# mfrhp.net
KiCad netlist of a schematic drawn in EAGLE
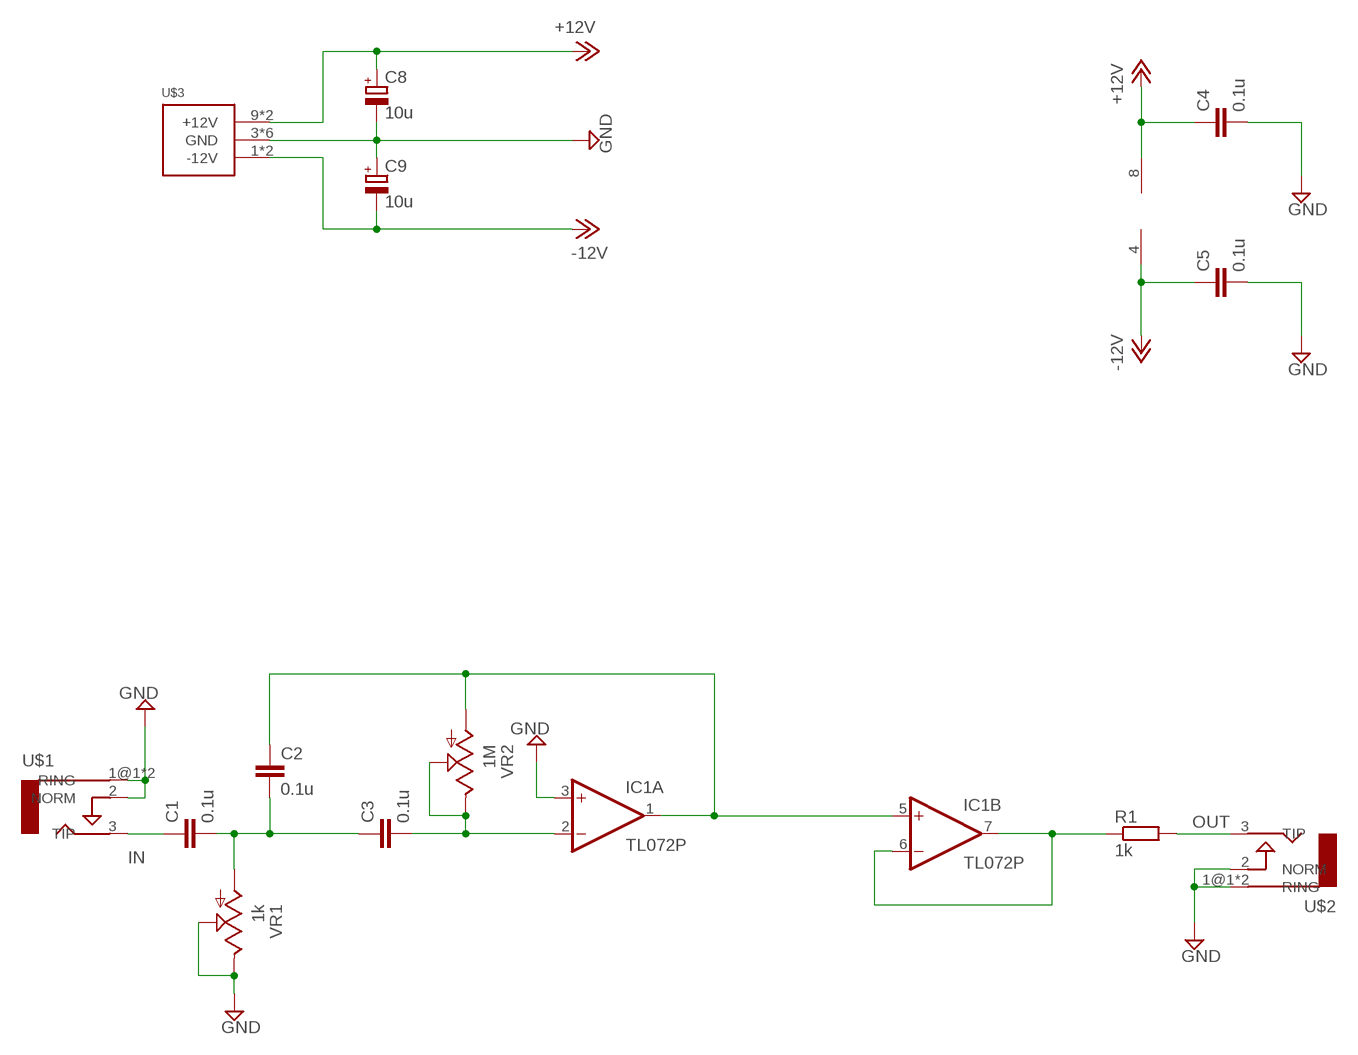
[diagram p0: schematic, sheet 1]

(export (version "E")
  (design (tool "Eeschema 10.0.6"))
  (components
    (comp (ref "C1")
      (value "0.1u")
      (footprint "eagle-import:C050-025X075")
      (libsource (lib "eagle-import") (part "C-EU050-025X075"))
    )
    (comp (ref "C2")
      (value "0.1u")
      (footprint "eagle-import:C050-025X075")
      (libsource (lib "eagle-import") (part "C-EU050-025X075"))
    )
    (comp (ref "C3")
      (value "0.1u")
      (footprint "eagle-import:C050-025X075")
      (libsource (lib "eagle-import") (part "C-EU050-025X075"))
    )
    (comp (ref "C4")
      (value "0.1u")
      (footprint "eagle-import:C025-025X050")
      (libsource (lib "eagle-import") (part "C-EU025-025X050"))
    )
    (comp (ref "C5")
      (value "0.1u")
      (footprint "eagle-import:C025-025X050")
      (libsource (lib "eagle-import") (part "C-EU025-025X050"))
    )
    (comp (ref "C8")
      (value "10u")
      (footprint "eagle-import:E2,5-5")
      (libsource (lib "eagle-import") (part "CPOL-EUE2.5-5"))
    )
    (comp (ref "C9")
      (value "10u")
      (footprint "eagle-import:E2,5-5")
      (libsource (lib "eagle-import") (part "CPOL-EUE2.5-5"))
    )
    (comp (ref "IC1")
      (value "TL072P")
      (footprint "eagle-import:DIL08")
      (libsource (lib "eagle-import") (part "TL072P"))
    )
    (comp (ref "R1")
      (value "1k")
      (footprint "eagle-import:0207_2V")
      (libsource (lib "eagle-import") (part "R-EU_0207/2V"))
    )
    (comp (ref "U$1")
      (value "AUDIO-JACKERTHENVAR")
      (footprint "eagle-import:ERTHENVAR-JACK")
      (libsource (lib "eagle-import") (part "AUDIO-JACKERTHENVAR"))
    )
    (comp (ref "U$2")
      (value "AUDIO-JACKERTHENVAR")
      (footprint "eagle-import:ERTHENVAR-JACK")
      (libsource (lib "eagle-import") (part "AUDIO-JACKERTHENVAR"))
    )
    (comp (ref "U$3")
      (value "POWER_SIMPLE10")
      (footprint "eagle-import:POWER_10")
      (libsource (lib "eagle-import") (part "POWER_SIMPLE10"))
    )
    (comp (ref "VR1")
      (value "1k")
      (footprint "eagle-import:9MM_SNAP-IN_POT")
      (libsource (lib "eagle-import") (part "9MM_SNAP-IN_POT_"))
    )
    (comp (ref "VR2")
      (value "1M")
      (footprint "eagle-import:9MM_SNAP-IN_POT")
      (libsource (lib "eagle-import") (part "9MM_SNAP-IN_POT_"))
    )
  )
  (nets
    (net (code "1") (name "+12V") (class "Default")
      (node (ref "C4") (pin "1") (pinfunction "1_1") (pintype "passive"))
      (node (ref "C8") (pin "+") (pinfunction "+_+") (pintype "passive"))
      (node (ref "IC1") (pin "8") (pinfunction "V+_8") (pintype "power_in"))
      (node (ref "U$3") (pin "10") (pinfunction "+12V_10") (pintype "bidirectional"))
      (node (ref "U$3") (pin "9") (pinfunction "+12V_9") (pintype "bidirectional"))
    )
    (net (code "2") (name "-12V") (class "Default")
      (node (ref "C5") (pin "1") (pinfunction "1_1") (pintype "passive"))
      (node (ref "C9") (pin "-") (pinfunction "-_-") (pintype "passive"))
      (node (ref "IC1") (pin "4") (pinfunction "V-_4") (pintype "power_in"))
      (node (ref "U$3") (pin "1") (pinfunction "-12V_1") (pintype "bidirectional"))
      (node (ref "U$3") (pin "2") (pinfunction "-12V_2") (pintype "bidirectional"))
    )
    (net (code "3") (name "/IN") (class "Default")
      (node (ref "C1") (pin "1") (pinfunction "1_1") (pintype "passive"))
      (node (ref "U$1") (pin "3") (pinfunction "TIP_3") (pintype "bidirectional"))
    )
    (net (code "4") (name "/OUT") (class "Default")
      (node (ref "R1") (pin "2") (pinfunction "2_2") (pintype "passive"))
      (node (ref "U$2") (pin "3") (pinfunction "TIP_3") (pintype "bidirectional"))
    )
    (net (code "5") (name "GND") (class "Default")
      (node (ref "C4") (pin "2") (pinfunction "2_2") (pintype "passive"))
      (node (ref "C5") (pin "2") (pinfunction "2_2") (pintype "passive"))
      (node (ref "C8") (pin "-") (pinfunction "-_-") (pintype "passive"))
      (node (ref "C9") (pin "+") (pinfunction "+_+") (pintype "passive"))
      (node (ref "IC1") (pin "3") (pinfunction "+IN_3") (pintype "input"))
      (node (ref "U$1") (pin "1@1") (pinfunction "RING_1@1") (pintype "bidirectional"))
      (node (ref "U$1") (pin "1@2") (pinfunction "RING_1@2") (pintype "bidirectional"))
      (node (ref "U$1") (pin "2") (pinfunction "NORM_2") (pintype "bidirectional"))
      (node (ref "U$2") (pin "1@1") (pinfunction "RING_1@1") (pintype "bidirectional"))
      (node (ref "U$2") (pin "1@2") (pinfunction "RING_1@2") (pintype "bidirectional"))
      (node (ref "U$2") (pin "2") (pinfunction "NORM_2") (pintype "bidirectional"))
      (node (ref "U$3") (pin "3") (pinfunction "GND_3") (pintype "bidirectional"))
      (node (ref "U$3") (pin "4") (pinfunction "GND_4") (pintype "bidirectional"))
      (node (ref "U$3") (pin "5") (pinfunction "GND_5") (pintype "bidirectional"))
      (node (ref "U$3") (pin "6") (pinfunction "GND_6") (pintype "bidirectional"))
      (node (ref "U$3") (pin "7") (pinfunction "GND_7") (pintype "bidirectional"))
      (node (ref "U$3") (pin "8") (pinfunction "GND_8") (pintype "bidirectional"))
      (node (ref "VR1") (pin "2") (pinfunction "S_2") (pintype "passive"))
      (node (ref "VR1") (pin "3") (pinfunction "E_3") (pintype "passive"))
    )
    (net (code "6") (name "Net-(IC1A--IN)") (class "Default")
      (node (ref "C3") (pin "2") (pinfunction "2_2") (pintype "passive"))
      (node (ref "IC1") (pin "2") (pinfunction "-IN_2") (pintype "input"))
      (node (ref "VR2") (pin "2") (pinfunction "S_2") (pintype "passive"))
      (node (ref "VR2") (pin "3") (pinfunction "E_3") (pintype "passive"))
    )
    (net (code "7") (name "Net-(IC1A-OUT)") (class "Default")
      (node (ref "C2") (pin "1") (pinfunction "1_1") (pintype "passive"))
      (node (ref "IC1") (pin "1") (pinfunction "OUT_1") (pintype "output"))
      (node (ref "IC1") (pin "5") (pinfunction "+IN_5") (pintype "input"))
      (node (ref "VR2") (pin "1") (pinfunction "A_1") (pintype "passive"))
    )
    (net (code "8") (name "Net-(IC1B--IN)") (class "Default")
      (node (ref "IC1") (pin "6") (pinfunction "-IN_6") (pintype "input"))
      (node (ref "IC1") (pin "7") (pinfunction "OUT_7") (pintype "output"))
      (node (ref "R1") (pin "1") (pinfunction "1_1") (pintype "passive"))
    )
    (net (code "9") (name "Net-(VR1-A)") (class "Default")
      (node (ref "C1") (pin "2") (pinfunction "2_2") (pintype "passive"))
      (node (ref "C2") (pin "2") (pinfunction "2_2") (pintype "passive"))
      (node (ref "C3") (pin "1") (pinfunction "1_1") (pintype "passive"))
      (node (ref "VR1") (pin "1") (pinfunction "A_1") (pintype "passive"))
    )
  )
)
